# CPU.net
KiCad netlist of a schematic drawn in Altium Designer
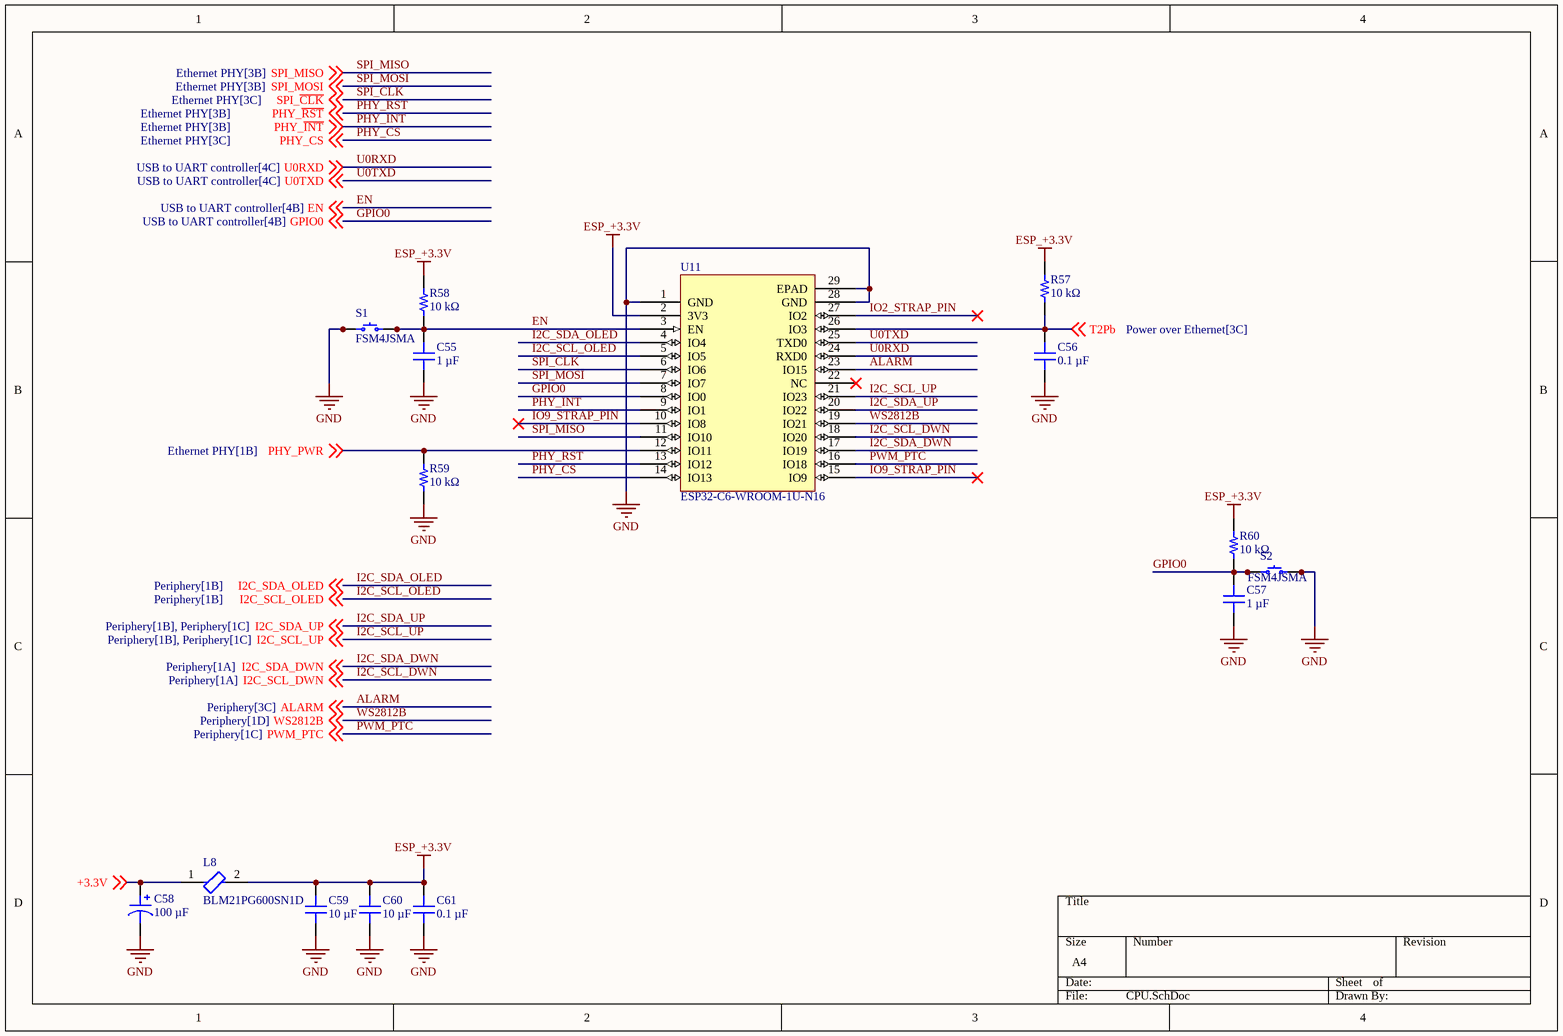
[diagram p0: CPU.SchDoc]

(export (version "E")
  (design (tool "Eeschema 10.0.6"))
  (components
    (comp (ref "C55")
      (value "1 µF")
      (footprint "CAP 0805_2012")
      (description "CAP CER 1UF 25V X7R 0805")
      (fields
        (field (name "PART NUMBER") "C2012X7R1E105K125AB")
        (field (name "CAPACITANCE") "1 µF")
        (field (name "MANUFACTURER") "TDK Corporation")
      )
      (libsource (lib "Celestial Altium Library - altium_library") (part "Capacitor"))
    )
    (comp (ref "C56")
      (value "0.1 µF")
      (footprint "CAP 0603_1608")
      (description "CAP CER 0.1UF 50V X7R 0603")
      (fields
        (field (name "PART NUMBER") "C1608X7R1H104K080AE")
        (field (name "CAPACITANCE") "0.1 µF")
        (field (name "MANUFACTURER") "TDK Corporation")
      )
      (libsource (lib "Celestial Altium Library - altium_library") (part "Capacitor"))
    )
    (comp (ref "C57")
      (value "1 µF")
      (footprint "CAP 0805_2012")
      (description "CAP CER 1UF 25V X7R 0805")
      (fields
        (field (name "PART NUMBER") "C2012X7R1E105K125AB")
        (field (name "CAPACITANCE") "1 µF")
        (field (name "MANUFACTURER") "TDK Corporation")
      )
      (libsource (lib "Celestial Altium Library - altium_library") (part "Capacitor"))
    )
    (comp (ref "C58")
      (value "100 µF")
      (footprint "CAP POL 1411_3528")
      (description "CAP TANT 100UF 20% 6.3V 1411")
      (fields (field (name "PART NUMBER") "T494B107M006AT") (field (name "MANUFACTURER") "KEMET"))
      (libsource (lib "Celestial Altium Library - altium_library") (part "Polarised Capacitor"))
    )
    (comp (ref "C59")
      (value "10 µF")
      (footprint "CAP 0805_2012")
      (description "CAP CER 10UF 6.3V X7R 0805")
      (fields
        (field (name "PART NUMBER") "CGA4J1X7R0J106K125AC")
        (field (name "CAPACITANCE") "10 µF")
        (field (name "MANUFACTURER") "TDK Corporation")
      )
      (libsource (lib "Celestial Altium Library - altium_library") (part "Capacitor"))
    )
    (comp (ref "C60")
      (value "10 µF")
      (footprint "CAP 0805_2012")
      (description "CAP CER 10UF 6.3V X7R 0805")
      (fields
        (field (name "PART NUMBER") "CGA4J1X7R0J106K125AC")
        (field (name "CAPACITANCE") "10 µF")
        (field (name "MANUFACTURER") "TDK Corporation")
      )
      (libsource (lib "Celestial Altium Library - altium_library") (part "Capacitor"))
    )
    (comp (ref "C61")
      (value "0.1 µF")
      (footprint "CAP 0603_1608")
      (description "CAP CER 0.1UF 50V X7R 0603")
      (fields
        (field (name "PART NUMBER") "C1608X7R1H104K080AE")
        (field (name "CAPACITANCE") "0.1 µF")
        (field (name "MANUFACTURER") "TDK Corporation")
      )
      (libsource (lib "Celestial Altium Library - altium_library") (part "Capacitor"))
    )
    (comp (ref "L8")
      (value "BLM21PG600SN1D")
      (footprint "FP-BLM21-0_2-t0_85-e0_5-d-IPC_A")
      (description "Chip Ferrite Bead, 0805, 60Ω @ 100MHz, 0.02Ω, 25%, 3.5A")
      (fields (field (name "TOLERANCE") "25%"))
      (libsource (lib "Altium Content Vault") (part "5f30dd21d616792df468990f7003faa"))
    )
    (comp (ref "R57")
      (value "10 kΩ")
      (footprint "RES 0603_1608")
      (description "RES SMD 10K OHM 1% 1/10W 0603")
      (fields (field (name "PART NUMBER") "CRCW060310K0FKEA") (field (name "MANUFACTURER") "Vishay Dale"))
      (libsource (lib "Celestial Altium Library - altium_library") (part "Resistor"))
    )
    (comp (ref "R58")
      (value "10 kΩ")
      (footprint "RES 0603_1608")
      (description "RES SMD 10K OHM 1% 1/10W 0603")
      (fields (field (name "PART NUMBER") "CRCW060310K0FKEA") (field (name "MANUFACTURER") "Vishay Dale"))
      (libsource (lib "Celestial Altium Library - altium_library") (part "Resistor"))
    )
    (comp (ref "R59")
      (value "10 kΩ")
      (footprint "RES 0603_1608")
      (description "RES SMD 10K OHM 1% 1/10W 0603")
      (fields (field (name "PART NUMBER") "CRCW060310K0FKEA") (field (name "MANUFACTURER") "Vishay Dale"))
      (libsource (lib "Celestial Altium Library - altium_library") (part "Resistor"))
    )
    (comp (ref "R60")
      (value "10 kΩ")
      (footprint "RES 0603_1608")
      (description "RES SMD 10K OHM 1% 1/10W 0603")
      (fields (field (name "PART NUMBER") "CRCW060310K0FKEA") (field (name "MANUFACTURER") "Vishay Dale"))
      (libsource (lib "Celestial Altium Library - altium_library") (part "Resistor"))
    )
    (comp (ref "S1")
      (value "FSM4JSMA")
      (footprint "TE FSM4JSMA")
      (description "SWITCH TACTILE SPST-NO 0.05A 24V")
      (fields (field (name "MANUFACTURER") "TE Connectivity ALCOSWITCH Switches"))
      (libsource (lib "Celestial Altium Library - altium_library") (part "SPST-NO 4 PIN"))
    )
    (comp (ref "S2")
      (value "FSM4JSMA")
      (footprint "TE FSM4JSMA")
      (description "SWITCH TACTILE SPST-NO 0.05A 24V")
      (fields (field (name "MANUFACTURER") "TE Connectivity ALCOSWITCH Switches"))
      (libsource (lib "Celestial Altium Library - altium_library") (part "SPST-NO 4 PIN"))
    )
    (comp (ref "U11")
      (value "ESP32-C6-WROOM-1U-N16")
      (footprint "ESP32-C6-WROOM-1U")
      (libsource (lib "SchLib") (part "ESP32-C6-WROOM-1U-N16"))
    )
  )
  (nets
    (net (code "1") (name "+3.3V") (class "Default")
      (node (ref "C58") (pin "1") (pinfunction "1_1") (pintype "passive"))
      (node (ref "L8") (pin "1") (pinfunction "1_1") (pintype "passive"))
    )
    (net (code "2") (name "/IO2_STRAP_PIN") (class "Default")
      (node (ref "U11") (pin "27") (pinfunction "IO2_27") (pintype "bidirectional+no_connect"))
    )
    (net (code "3") (name "/IO9_STRAP_PIN") (class "Default")
      (node (ref "U11") (pin "10") (pinfunction "IO8_10") (pintype "bidirectional"))
      (node (ref "U11") (pin "15") (pinfunction "IO9_15") (pintype "bidirectional"))
    )
    (net (code "4") (name "ALARM") (class "Default")
      (node (ref "U11") (pin "23") (pinfunction "IO15_23") (pintype "bidirectional"))
    )
    (net (code "5") (name "EN") (class "Default")
      (node (ref "C55") (pin "2") (pinfunction "2_2") (pintype "passive"))
      (node (ref "R58") (pin "1") (pinfunction "1_1") (pintype "passive"))
      (node (ref "S1") (pin "3") (pinfunction "3_3") (pintype "passive"))
      (node (ref "S1") (pin "4") (pinfunction "4_4") (pintype "passive"))
      (node (ref "U11") (pin "3") (pinfunction "EN_3") (pintype "input"))
    )
    (net (code "6") (name "ESP_+3.3V") (class "Default")
      (node (ref "C59") (pin "2") (pinfunction "2_2") (pintype "passive"))
      (node (ref "C60") (pin "2") (pinfunction "2_2") (pintype "passive"))
      (node (ref "C61") (pin "2") (pinfunction "2_2") (pintype "passive"))
      (node (ref "L8") (pin "2") (pinfunction "2_2") (pintype "passive"))
      (node (ref "R57") (pin "2") (pinfunction "2_2") (pintype "passive"))
      (node (ref "R58") (pin "2") (pinfunction "2_2") (pintype "passive"))
      (node (ref "R60") (pin "2") (pinfunction "2_2") (pintype "passive"))
      (node (ref "U11") (pin "2") (pinfunction "3V3_2") (pintype "passive"))
    )
    (net (code "7") (name "GND") (class "Default")
      (node (ref "C55") (pin "1") (pinfunction "1_1") (pintype "passive"))
      (node (ref "C56") (pin "1") (pinfunction "1_1") (pintype "passive"))
      (node (ref "C57") (pin "1") (pinfunction "1_1") (pintype "passive"))
      (node (ref "C58") (pin "2") (pinfunction "2_2") (pintype "passive"))
      (node (ref "C59") (pin "1") (pinfunction "1_1") (pintype "passive"))
      (node (ref "C60") (pin "1") (pinfunction "1_1") (pintype "passive"))
      (node (ref "C61") (pin "1") (pinfunction "1_1") (pintype "passive"))
      (node (ref "R59") (pin "1") (pinfunction "1_1") (pintype "passive"))
      (node (ref "S1") (pin "1") (pinfunction "1_1") (pintype "passive"))
      (node (ref "S1") (pin "2") (pinfunction "2_2") (pintype "passive"))
      (node (ref "S2") (pin "3") (pinfunction "3_3") (pintype "passive"))
      (node (ref "S2") (pin "4") (pinfunction "4_4") (pintype "passive"))
      (node (ref "U11") (pin "1") (pinfunction "GND_1") (pintype "passive"))
      (node (ref "U11") (pin "28") (pinfunction "GND_28") (pintype "passive"))
      (node (ref "U11") (pin "29") (pinfunction "EPAD_29") (pintype "passive"))
    )
    (net (code "8") (name "GPIO0") (class "Default")
      (node (ref "C57") (pin "2") (pinfunction "2_2") (pintype "passive"))
      (node (ref "R60") (pin "1") (pinfunction "1_1") (pintype "passive"))
      (node (ref "S2") (pin "1") (pinfunction "1_1") (pintype "passive"))
      (node (ref "S2") (pin "2") (pinfunction "2_2") (pintype "passive"))
      (node (ref "U11") (pin "8") (pinfunction "IO0_8") (pintype "bidirectional"))
    )
    (net (code "9") (name "I2C_SCL_DWN") (class "Default")
      (node (ref "U11") (pin "18") (pinfunction "IO20_18") (pintype "bidirectional"))
    )
    (net (code "10") (name "I2C_SCL_OLED") (class "Default")
      (node (ref "U11") (pin "5") (pinfunction "IO5_5") (pintype "bidirectional"))
    )
    (net (code "11") (name "I2C_SCL_UP") (class "Default")
      (node (ref "U11") (pin "21") (pinfunction "IO23_21") (pintype "bidirectional"))
    )
    (net (code "12") (name "I2C_SDA_DWN") (class "Default")
      (node (ref "U11") (pin "17") (pinfunction "IO19_17") (pintype "bidirectional"))
    )
    (net (code "13") (name "I2C_SDA_OLED") (class "Default")
      (node (ref "U11") (pin "4") (pinfunction "IO4_4") (pintype "bidirectional"))
    )
    (net (code "14") (name "I2C_SDA_UP") (class "Default")
      (node (ref "U11") (pin "20") (pinfunction "IO22_20") (pintype "bidirectional"))
    )
    (net (code "15") (name "PHY_CS") (class "Default")
      (node (ref "U11") (pin "14") (pinfunction "IO13_14") (pintype "bidirectional"))
    )
    (net (code "16") (name "PHY_PWR") (class "Default")
      (node (ref "R59") (pin "2") (pinfunction "2_2") (pintype "passive"))
      (node (ref "U11") (pin "12") (pinfunction "IO11_12") (pintype "bidirectional"))
    )
    (net (code "17") (name "PHY_~{INT}") (class "Default")
      (node (ref "U11") (pin "9") (pinfunction "IO1_9") (pintype "bidirectional"))
    )
    (net (code "18") (name "PHY_~{RST}") (class "Default")
      (node (ref "U11") (pin "13") (pinfunction "IO12_13") (pintype "bidirectional"))
    )
    (net (code "19") (name "PWM_PTC") (class "Default")
      (node (ref "U11") (pin "16") (pinfunction "IO18_16") (pintype "bidirectional"))
    )
    (net (code "20") (name "SPI_MISO") (class "Default")
      (node (ref "U11") (pin "11") (pinfunction "IO10_11") (pintype "bidirectional"))
    )
    (net (code "21") (name "SPI_MOSI") (class "Default")
      (node (ref "U11") (pin "7") (pinfunction "IO7_7") (pintype "bidirectional"))
    )
    (net (code "22") (name "SPI_~{CLK}") (class "Default")
      (node (ref "U11") (pin "6") (pinfunction "IO6_6") (pintype "bidirectional"))
    )
    (net (code "23") (name "T2Pb") (class "Default")
      (node (ref "C56") (pin "2") (pinfunction "2_2") (pintype "passive"))
      (node (ref "R57") (pin "1") (pinfunction "1_1") (pintype "passive"))
      (node (ref "U11") (pin "26") (pinfunction "IO3_26") (pintype "bidirectional"))
    )
    (net (code "24") (name "U0RXD") (class "Default")
      (node (ref "U11") (pin "24") (pinfunction "RXD0_24") (pintype "bidirectional"))
    )
    (net (code "25") (name "U0TXD") (class "Default")
      (node (ref "U11") (pin "25") (pinfunction "TXD0_25") (pintype "bidirectional"))
    )
    (net (code "26") (name "WS2812B") (class "Default")
      (node (ref "U11") (pin "19") (pinfunction "IO21_19") (pintype "bidirectional"))
    )
    (net (code "27") (name "unconnected-(U11-NC-Pad22)") (class "Default")
      (node (ref "U11") (pin "22") (pinfunction "NC_22") (pintype "passive+no_connect"))
    )
  )
)
